# Switching_and_Pico.net
KiCad netlist of a schematic drawn in EAGLE
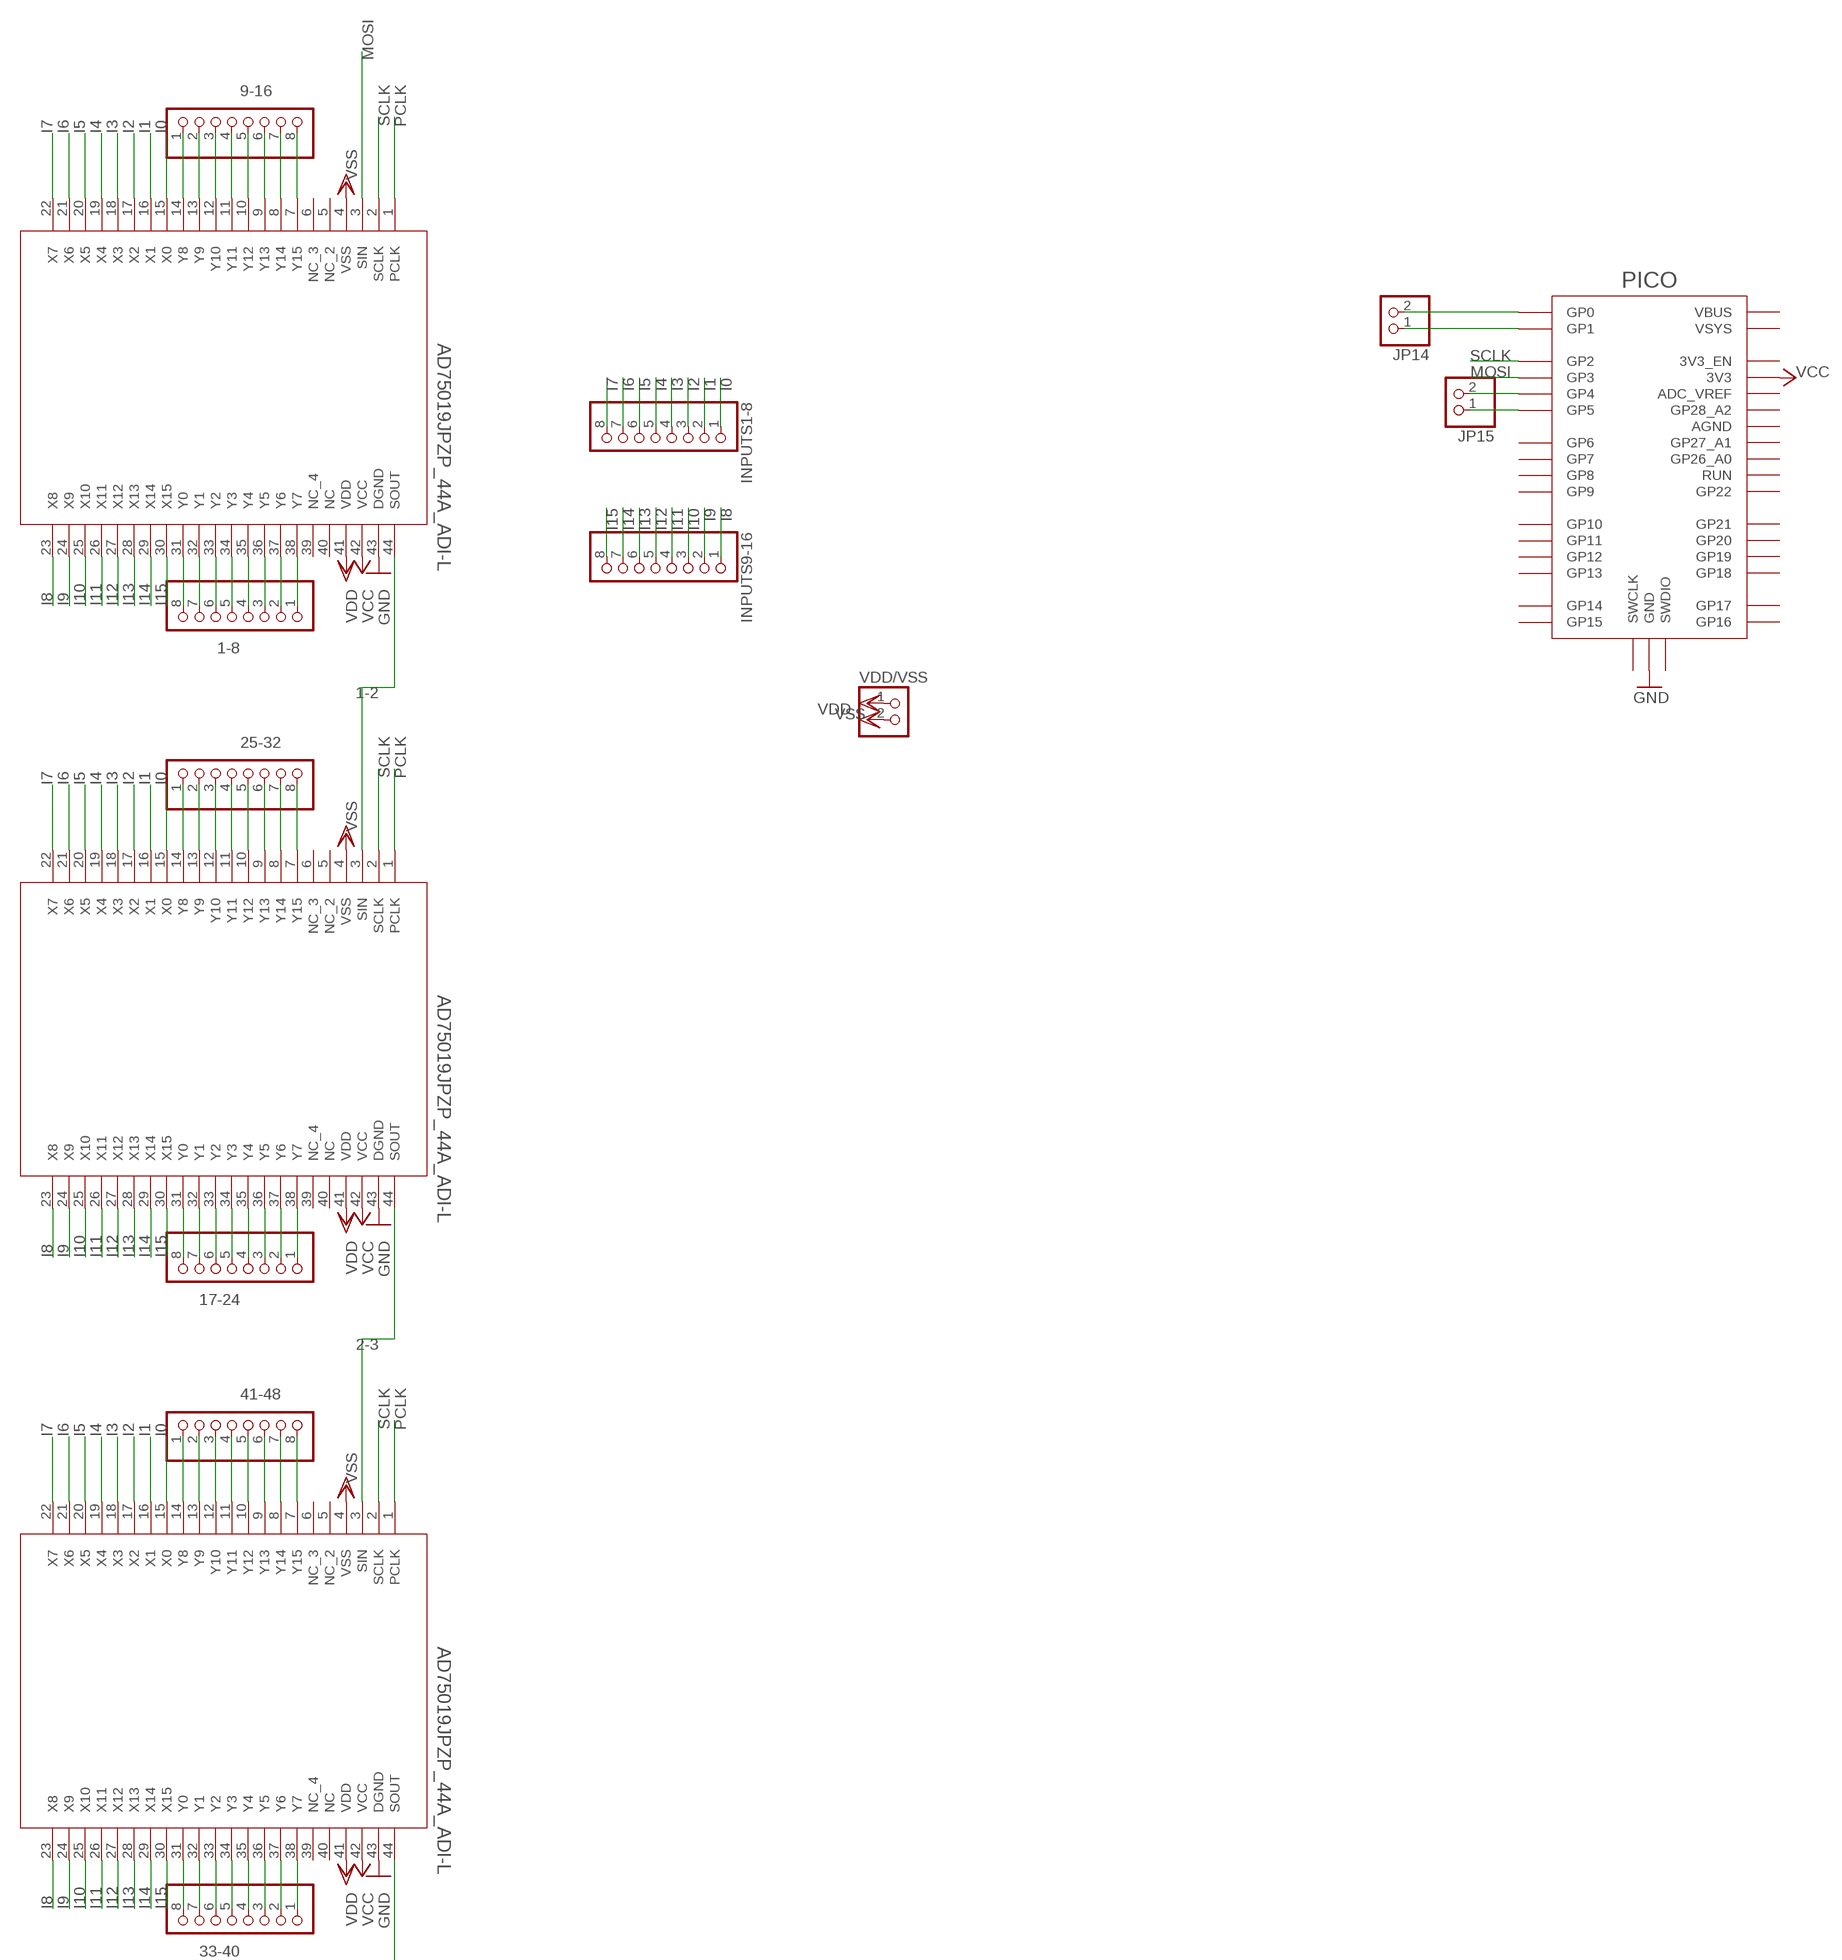
[diagram p0: schematic, sheet 1, part 1 of 2]
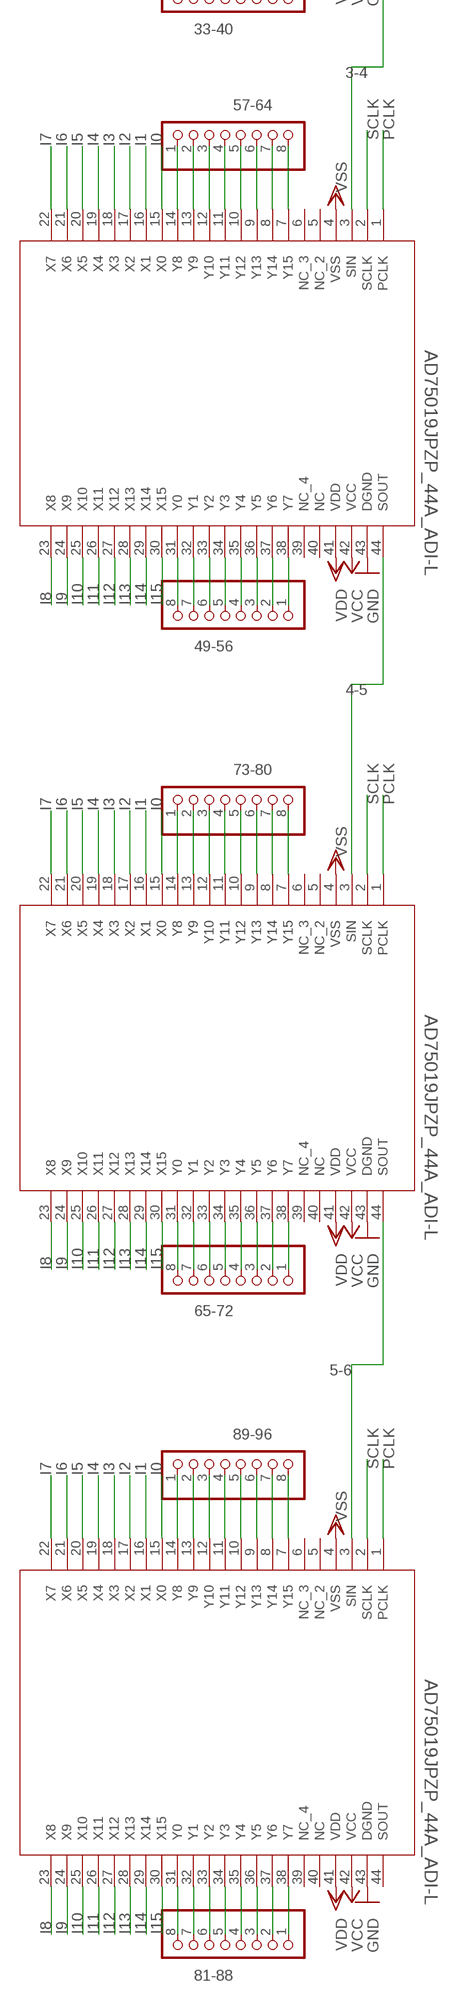
[diagram p1: schematic, sheet 1, part 2 of 2]

(export (version "E")
  (design (tool "Eeschema 10.0.6"))
  (components
    (comp (ref "1-8")
      (value "PINHD-1X8")
      (footprint "eagle-import:1X08")
      (libsource (lib "eagle-import") (part "PINHD-1X8"))
    )
    (comp (ref "9-16")
      (value "PINHD-1X8")
      (footprint "eagle-import:1X08")
      (libsource (lib "eagle-import") (part "PINHD-1X8"))
    )
    (comp (ref "17-24")
      (value "PINHD-1X8")
      (footprint "eagle-import:1X08")
      (libsource (lib "eagle-import") (part "PINHD-1X8"))
    )
    (comp (ref "25-32")
      (value "PINHD-1X8")
      (footprint "eagle-import:1X08")
      (libsource (lib "eagle-import") (part "PINHD-1X8"))
    )
    (comp (ref "33-40")
      (value "PINHD-1X8")
      (footprint "eagle-import:1X08")
      (libsource (lib "eagle-import") (part "PINHD-1X8"))
    )
    (comp (ref "41-48")
      (value "PINHD-1X8")
      (footprint "eagle-import:1X08")
      (libsource (lib "eagle-import") (part "PINHD-1X8"))
    )
    (comp (ref "49-56")
      (value "PINHD-1X8")
      (footprint "eagle-import:1X08")
      (libsource (lib "eagle-import") (part "PINHD-1X8"))
    )
    (comp (ref "57-64")
      (value "PINHD-1X8")
      (footprint "eagle-import:1X08")
      (libsource (lib "eagle-import") (part "PINHD-1X8"))
    )
    (comp (ref "65-72")
      (value "PINHD-1X8")
      (footprint "eagle-import:1X08")
      (libsource (lib "eagle-import") (part "PINHD-1X8"))
    )
    (comp (ref "73-80")
      (value "PINHD-1X8")
      (footprint "eagle-import:1X08")
      (libsource (lib "eagle-import") (part "PINHD-1X8"))
    )
    (comp (ref "81-88")
      (value "PINHD-1X8")
      (footprint "eagle-import:1X08")
      (libsource (lib "eagle-import") (part "PINHD-1X8"))
    )
    (comp (ref "89-96")
      (value "PINHD-1X8")
      (footprint "eagle-import:1X08")
      (libsource (lib "eagle-import") (part "PINHD-1X8"))
    )
    (comp (ref "INPUTS1-8")
      (value "PINHD-1X8")
      (footprint "eagle-import:1X08")
      (libsource (lib "eagle-import") (part "PINHD-1X8"))
    )
    (comp (ref "INPUTS9-16")
      (value "PINHD-1X8")
      (footprint "eagle-import:1X08")
      (libsource (lib "eagle-import") (part "PINHD-1X8"))
    )
    (comp (ref "JP14")
      (value "PINHD-1X2")
      (footprint "eagle-import:1X02")
      (libsource (lib "eagle-import") (part "PINHD-1X2"))
    )
    (comp (ref "JP15")
      (value "PINHD-1X2")
      (footprint "eagle-import:1X02")
      (libsource (lib "eagle-import") (part "PINHD-1X2"))
    )
    (comp (ref "PICO")
      (value "RPI_PICO-TH")
      (footprint "eagle-import:RPI_PICO_TH")
      (libsource (lib "eagle-import") (part "RPI_PICO-TH"))
    )
    (comp (ref "SWITCH1")
      (value "AD75019JPZP_44A_ADI-L")
      (footprint "eagle-import:P_44A_ADI-L")
      (fields
        (field (name "MANUFACTURER_PART_NUMBER") "AD75019JPZ")
        (field (name "COPYRIGHT") "Copyright (C) 2024 Ultra Librarian. All rights reserved.")
      )
      (libsource (lib "eagle-import") (part "AD75019JPZP_44A_ADI-L"))
    )
    (comp (ref "SWITCH2")
      (value "AD75019JPZP_44A_ADI-L")
      (footprint "eagle-import:P_44A_ADI-L")
      (fields
        (field (name "MANUFACTURER_PART_NUMBER") "AD75019JPZ")
        (field (name "COPYRIGHT") "Copyright (C) 2024 Ultra Librarian. All rights reserved.")
      )
      (libsource (lib "eagle-import") (part "AD75019JPZP_44A_ADI-L"))
    )
    (comp (ref "SWITCH3")
      (value "AD75019JPZP_44A_ADI-L")
      (footprint "eagle-import:P_44A_ADI-L")
      (fields
        (field (name "MANUFACTURER_PART_NUMBER") "AD75019JPZ")
        (field (name "COPYRIGHT") "Copyright (C) 2024 Ultra Librarian. All rights reserved.")
      )
      (libsource (lib "eagle-import") (part "AD75019JPZP_44A_ADI-L"))
    )
    (comp (ref "SWITCH4")
      (value "AD75019JPZP_44A_ADI-L")
      (footprint "eagle-import:P_44A_ADI-L")
      (fields
        (field (name "MANUFACTURER_PART_NUMBER") "AD75019JPZ")
        (field (name "COPYRIGHT") "Copyright (C) 2024 Ultra Librarian. All rights reserved.")
      )
      (libsource (lib "eagle-import") (part "AD75019JPZP_44A_ADI-L"))
    )
    (comp (ref "SWITCH5")
      (value "AD75019JPZP_44A_ADI-L")
      (footprint "eagle-import:P_44A_ADI-L")
      (fields
        (field (name "MANUFACTURER_PART_NUMBER") "AD75019JPZ")
        (field (name "COPYRIGHT") "Copyright (C) 2024 Ultra Librarian. All rights reserved.")
      )
      (libsource (lib "eagle-import") (part "AD75019JPZP_44A_ADI-L"))
    )
    (comp (ref "SWITCH6")
      (value "AD75019JPZP_44A_ADI-L")
      (footprint "eagle-import:P_44A_ADI-L")
      (fields
        (field (name "MANUFACTURER_PART_NUMBER") "AD75019JPZ")
        (field (name "COPYRIGHT") "Copyright (C) 2024 Ultra Librarian. All rights reserved.")
      )
      (libsource (lib "eagle-import") (part "AD75019JPZP_44A_ADI-L"))
    )
    (comp (ref "VDD/VSS")
      (value "PINHD-1X2")
      (footprint "eagle-import:1X02")
      (libsource (lib "eagle-import") (part "PINHD-1X2"))
    )
  )
  (nets
    (net (code "1") (name "/1-2") (class "Default")
      (node (ref "SWITCH1") (pin "44") (pinfunction "SOUT_44") (pintype "passive"))
      (node (ref "SWITCH2") (pin "3") (pinfunction "SIN_3") (pintype "passive"))
    )
    (net (code "2") (name "/2-3") (class "Default")
      (node (ref "SWITCH2") (pin "44") (pinfunction "SOUT_44") (pintype "passive"))
      (node (ref "SWITCH3") (pin "3") (pinfunction "SIN_3") (pintype "passive"))
    )
    (net (code "3") (name "/3-4") (class "Default")
      (node (ref "SWITCH3") (pin "44") (pinfunction "SOUT_44") (pintype "passive"))
      (node (ref "SWITCH4") (pin "3") (pinfunction "SIN_3") (pintype "passive"))
    )
    (net (code "4") (name "/4-5") (class "Default")
      (node (ref "SWITCH4") (pin "44") (pinfunction "SOUT_44") (pintype "passive"))
      (node (ref "SWITCH5") (pin "3") (pinfunction "SIN_3") (pintype "passive"))
    )
    (net (code "5") (name "/5-6") (class "Default")
      (node (ref "SWITCH5") (pin "44") (pinfunction "SOUT_44") (pintype "passive"))
      (node (ref "SWITCH6") (pin "3") (pinfunction "SIN_3") (pintype "passive"))
    )
    (net (code "6") (name "/I0") (class "Default")
      (node (ref "INPUTS1-8") (pin "1") (pinfunction "1_1") (pintype "passive"))
      (node (ref "SWITCH1") (pin "15") (pinfunction "X0_15") (pintype "passive"))
      (node (ref "SWITCH2") (pin "15") (pinfunction "X0_15") (pintype "passive"))
      (node (ref "SWITCH3") (pin "15") (pinfunction "X0_15") (pintype "passive"))
      (node (ref "SWITCH4") (pin "15") (pinfunction "X0_15") (pintype "passive"))
      (node (ref "SWITCH5") (pin "15") (pinfunction "X0_15") (pintype "passive"))
      (node (ref "SWITCH6") (pin "15") (pinfunction "X0_15") (pintype "passive"))
    )
    (net (code "7") (name "/I1") (class "Default")
      (node (ref "INPUTS1-8") (pin "2") (pinfunction "2_2") (pintype "passive"))
      (node (ref "SWITCH1") (pin "16") (pinfunction "X1_16") (pintype "passive"))
      (node (ref "SWITCH2") (pin "16") (pinfunction "X1_16") (pintype "passive"))
      (node (ref "SWITCH3") (pin "16") (pinfunction "X1_16") (pintype "passive"))
      (node (ref "SWITCH4") (pin "16") (pinfunction "X1_16") (pintype "passive"))
      (node (ref "SWITCH5") (pin "16") (pinfunction "X1_16") (pintype "passive"))
      (node (ref "SWITCH6") (pin "16") (pinfunction "X1_16") (pintype "passive"))
    )
    (net (code "8") (name "/I2") (class "Default")
      (node (ref "INPUTS1-8") (pin "3") (pinfunction "3_3") (pintype "passive"))
      (node (ref "SWITCH1") (pin "17") (pinfunction "X2_17") (pintype "passive"))
      (node (ref "SWITCH2") (pin "17") (pinfunction "X2_17") (pintype "passive"))
      (node (ref "SWITCH3") (pin "17") (pinfunction "X2_17") (pintype "passive"))
      (node (ref "SWITCH4") (pin "17") (pinfunction "X2_17") (pintype "passive"))
      (node (ref "SWITCH5") (pin "17") (pinfunction "X2_17") (pintype "passive"))
      (node (ref "SWITCH6") (pin "17") (pinfunction "X2_17") (pintype "passive"))
    )
    (net (code "9") (name "/I3") (class "Default")
      (node (ref "INPUTS1-8") (pin "4") (pinfunction "4_4") (pintype "passive"))
      (node (ref "SWITCH1") (pin "18") (pinfunction "X3_18") (pintype "passive"))
      (node (ref "SWITCH2") (pin "18") (pinfunction "X3_18") (pintype "passive"))
      (node (ref "SWITCH3") (pin "18") (pinfunction "X3_18") (pintype "passive"))
      (node (ref "SWITCH4") (pin "18") (pinfunction "X3_18") (pintype "passive"))
      (node (ref "SWITCH5") (pin "18") (pinfunction "X3_18") (pintype "passive"))
      (node (ref "SWITCH6") (pin "18") (pinfunction "X3_18") (pintype "passive"))
    )
    (net (code "10") (name "/I4") (class "Default")
      (node (ref "INPUTS1-8") (pin "5") (pinfunction "5_5") (pintype "passive"))
      (node (ref "SWITCH1") (pin "19") (pinfunction "X4_19") (pintype "passive"))
      (node (ref "SWITCH2") (pin "19") (pinfunction "X4_19") (pintype "passive"))
      (node (ref "SWITCH3") (pin "19") (pinfunction "X4_19") (pintype "passive"))
      (node (ref "SWITCH4") (pin "19") (pinfunction "X4_19") (pintype "passive"))
      (node (ref "SWITCH5") (pin "19") (pinfunction "X4_19") (pintype "passive"))
      (node (ref "SWITCH6") (pin "19") (pinfunction "X4_19") (pintype "passive"))
    )
    (net (code "11") (name "/I5") (class "Default")
      (node (ref "INPUTS1-8") (pin "6") (pinfunction "6_6") (pintype "passive"))
      (node (ref "SWITCH1") (pin "20") (pinfunction "X5_20") (pintype "passive"))
      (node (ref "SWITCH2") (pin "20") (pinfunction "X5_20") (pintype "passive"))
      (node (ref "SWITCH3") (pin "20") (pinfunction "X5_20") (pintype "passive"))
      (node (ref "SWITCH4") (pin "20") (pinfunction "X5_20") (pintype "passive"))
      (node (ref "SWITCH5") (pin "20") (pinfunction "X5_20") (pintype "passive"))
      (node (ref "SWITCH6") (pin "20") (pinfunction "X5_20") (pintype "passive"))
    )
    (net (code "12") (name "/I6") (class "Default")
      (node (ref "INPUTS1-8") (pin "7") (pinfunction "7_7") (pintype "passive"))
      (node (ref "SWITCH1") (pin "21") (pinfunction "X6_21") (pintype "passive"))
      (node (ref "SWITCH2") (pin "21") (pinfunction "X6_21") (pintype "passive"))
      (node (ref "SWITCH3") (pin "21") (pinfunction "X6_21") (pintype "passive"))
      (node (ref "SWITCH4") (pin "21") (pinfunction "X6_21") (pintype "passive"))
      (node (ref "SWITCH5") (pin "21") (pinfunction "X6_21") (pintype "passive"))
      (node (ref "SWITCH6") (pin "21") (pinfunction "X6_21") (pintype "passive"))
    )
    (net (code "13") (name "/I7") (class "Default")
      (node (ref "INPUTS1-8") (pin "8") (pinfunction "8_8") (pintype "passive"))
      (node (ref "SWITCH1") (pin "22") (pinfunction "X7_22") (pintype "passive"))
      (node (ref "SWITCH2") (pin "22") (pinfunction "X7_22") (pintype "passive"))
      (node (ref "SWITCH3") (pin "22") (pinfunction "X7_22") (pintype "passive"))
      (node (ref "SWITCH4") (pin "22") (pinfunction "X7_22") (pintype "passive"))
      (node (ref "SWITCH5") (pin "22") (pinfunction "X7_22") (pintype "passive"))
      (node (ref "SWITCH6") (pin "22") (pinfunction "X7_22") (pintype "passive"))
    )
    (net (code "14") (name "/I8") (class "Default")
      (node (ref "INPUTS9-16") (pin "1") (pinfunction "1_1") (pintype "passive"))
      (node (ref "SWITCH1") (pin "23") (pinfunction "X8_23") (pintype "passive"))
      (node (ref "SWITCH2") (pin "23") (pinfunction "X8_23") (pintype "passive"))
      (node (ref "SWITCH3") (pin "23") (pinfunction "X8_23") (pintype "passive"))
      (node (ref "SWITCH4") (pin "23") (pinfunction "X8_23") (pintype "passive"))
      (node (ref "SWITCH5") (pin "23") (pinfunction "X8_23") (pintype "passive"))
      (node (ref "SWITCH6") (pin "23") (pinfunction "X8_23") (pintype "passive"))
    )
    (net (code "15") (name "/I9") (class "Default")
      (node (ref "INPUTS9-16") (pin "2") (pinfunction "2_2") (pintype "passive"))
      (node (ref "SWITCH1") (pin "24") (pinfunction "X9_24") (pintype "passive"))
      (node (ref "SWITCH2") (pin "24") (pinfunction "X9_24") (pintype "passive"))
      (node (ref "SWITCH3") (pin "24") (pinfunction "X9_24") (pintype "passive"))
      (node (ref "SWITCH4") (pin "24") (pinfunction "X9_24") (pintype "passive"))
      (node (ref "SWITCH5") (pin "24") (pinfunction "X9_24") (pintype "passive"))
      (node (ref "SWITCH6") (pin "24") (pinfunction "X9_24") (pintype "passive"))
    )
    (net (code "16") (name "/I10") (class "Default")
      (node (ref "INPUTS9-16") (pin "3") (pinfunction "3_3") (pintype "passive"))
      (node (ref "SWITCH1") (pin "25") (pinfunction "X10_25") (pintype "passive"))
      (node (ref "SWITCH2") (pin "25") (pinfunction "X10_25") (pintype "passive"))
      (node (ref "SWITCH3") (pin "25") (pinfunction "X10_25") (pintype "passive"))
      (node (ref "SWITCH4") (pin "25") (pinfunction "X10_25") (pintype "passive"))
      (node (ref "SWITCH5") (pin "25") (pinfunction "X10_25") (pintype "passive"))
      (node (ref "SWITCH6") (pin "25") (pinfunction "X10_25") (pintype "passive"))
    )
    (net (code "17") (name "/I11") (class "Default")
      (node (ref "INPUTS9-16") (pin "4") (pinfunction "4_4") (pintype "passive"))
      (node (ref "SWITCH1") (pin "26") (pinfunction "X11_26") (pintype "passive"))
      (node (ref "SWITCH2") (pin "26") (pinfunction "X11_26") (pintype "passive"))
      (node (ref "SWITCH3") (pin "26") (pinfunction "X11_26") (pintype "passive"))
      (node (ref "SWITCH4") (pin "26") (pinfunction "X11_26") (pintype "passive"))
      (node (ref "SWITCH5") (pin "26") (pinfunction "X11_26") (pintype "passive"))
      (node (ref "SWITCH6") (pin "26") (pinfunction "X11_26") (pintype "passive"))
    )
    (net (code "18") (name "/I12") (class "Default")
      (node (ref "INPUTS9-16") (pin "5") (pinfunction "5_5") (pintype "passive"))
      (node (ref "SWITCH1") (pin "27") (pinfunction "X12_27") (pintype "passive"))
      (node (ref "SWITCH2") (pin "27") (pinfunction "X12_27") (pintype "passive"))
      (node (ref "SWITCH3") (pin "27") (pinfunction "X12_27") (pintype "passive"))
      (node (ref "SWITCH4") (pin "27") (pinfunction "X12_27") (pintype "passive"))
      (node (ref "SWITCH5") (pin "27") (pinfunction "X12_27") (pintype "passive"))
      (node (ref "SWITCH6") (pin "27") (pinfunction "X12_27") (pintype "passive"))
    )
    (net (code "19") (name "/I13") (class "Default")
      (node (ref "INPUTS9-16") (pin "6") (pinfunction "6_6") (pintype "passive"))
      (node (ref "SWITCH1") (pin "28") (pinfunction "X13_28") (pintype "passive"))
      (node (ref "SWITCH2") (pin "28") (pinfunction "X13_28") (pintype "passive"))
      (node (ref "SWITCH3") (pin "28") (pinfunction "X13_28") (pintype "passive"))
      (node (ref "SWITCH4") (pin "28") (pinfunction "X13_28") (pintype "passive"))
      (node (ref "SWITCH5") (pin "28") (pinfunction "X13_28") (pintype "passive"))
      (node (ref "SWITCH6") (pin "28") (pinfunction "X13_28") (pintype "passive"))
    )
    (net (code "20") (name "/I14") (class "Default")
      (node (ref "INPUTS9-16") (pin "7") (pinfunction "7_7") (pintype "passive"))
      (node (ref "SWITCH1") (pin "29") (pinfunction "X14_29") (pintype "passive"))
      (node (ref "SWITCH2") (pin "29") (pinfunction "X14_29") (pintype "passive"))
      (node (ref "SWITCH3") (pin "29") (pinfunction "X14_29") (pintype "passive"))
      (node (ref "SWITCH4") (pin "29") (pinfunction "X14_29") (pintype "passive"))
      (node (ref "SWITCH5") (pin "29") (pinfunction "X14_29") (pintype "passive"))
      (node (ref "SWITCH6") (pin "29") (pinfunction "X14_29") (pintype "passive"))
    )
    (net (code "21") (name "/I15") (class "Default")
      (node (ref "INPUTS9-16") (pin "8") (pinfunction "8_8") (pintype "passive"))
      (node (ref "SWITCH1") (pin "30") (pinfunction "X15_30") (pintype "passive"))
      (node (ref "SWITCH2") (pin "30") (pinfunction "X15_30") (pintype "passive"))
      (node (ref "SWITCH3") (pin "30") (pinfunction "X15_30") (pintype "passive"))
      (node (ref "SWITCH4") (pin "30") (pinfunction "X15_30") (pintype "passive"))
      (node (ref "SWITCH5") (pin "30") (pinfunction "X15_30") (pintype "passive"))
      (node (ref "SWITCH6") (pin "30") (pinfunction "X15_30") (pintype "passive"))
    )
    (net (code "22") (name "/MOSI") (class "Default")
      (node (ref "PICO") (pin "GP3") (pinfunction "GP3_GP3") (pintype "bidirectional"))
      (node (ref "SWITCH1") (pin "3") (pinfunction "SIN_3") (pintype "passive"))
    )
    (net (code "23") (name "/PCLK") (class "Default")
      (node (ref "SWITCH1") (pin "1") (pinfunction "PCLK_1") (pintype "passive"))
      (node (ref "SWITCH2") (pin "1") (pinfunction "PCLK_1") (pintype "passive"))
      (node (ref "SWITCH3") (pin "1") (pinfunction "PCLK_1") (pintype "passive"))
      (node (ref "SWITCH4") (pin "1") (pinfunction "PCLK_1") (pintype "passive"))
      (node (ref "SWITCH5") (pin "1") (pinfunction "PCLK_1") (pintype "passive"))
      (node (ref "SWITCH6") (pin "1") (pinfunction "PCLK_1") (pintype "passive"))
    )
    (net (code "24") (name "/SCLK") (class "Default")
      (node (ref "PICO") (pin "GP2") (pinfunction "GP2_GP2") (pintype "bidirectional"))
      (node (ref "SWITCH1") (pin "2") (pinfunction "SCLK_2") (pintype "passive"))
      (node (ref "SWITCH2") (pin "2") (pinfunction "SCLK_2") (pintype "passive"))
      (node (ref "SWITCH3") (pin "2") (pinfunction "SCLK_2") (pintype "passive"))
      (node (ref "SWITCH4") (pin "2") (pinfunction "SCLK_2") (pintype "passive"))
      (node (ref "SWITCH5") (pin "2") (pinfunction "SCLK_2") (pintype "passive"))
      (node (ref "SWITCH6") (pin "2") (pinfunction "SCLK_2") (pintype "passive"))
    )
    (net (code "25") (name "GND") (class "Default")
      (node (ref "PICO") (pin "GND@1") (pinfunction "GND_GND@1") (pintype "bidirectional"))
      (node (ref "PICO") (pin "GND@2") (pinfunction "GND_GND@2") (pintype "bidirectional"))
      (node (ref "PICO") (pin "GND@3") (pinfunction "GND_GND@3") (pintype "bidirectional"))
      (node (ref "PICO") (pin "GND@4") (pinfunction "GND_GND@4") (pintype "bidirectional"))
      (node (ref "PICO") (pin "GND@5") (pinfunction "GND_GND@5") (pintype "bidirectional"))
      (node (ref "PICO") (pin "GND@6") (pinfunction "GND_GND@6") (pintype "bidirectional"))
      (node (ref "PICO") (pin "GND@7") (pinfunction "GND_GND@7") (pintype "bidirectional"))
      (node (ref "PICO") (pin "GND@8") (pinfunction "GND_GND@8") (pintype "bidirectional"))
      (node (ref "SWITCH1") (pin "43") (pinfunction "DGND_43") (pintype "passive"))
      (node (ref "SWITCH2") (pin "43") (pinfunction "DGND_43") (pintype "passive"))
      (node (ref "SWITCH3") (pin "43") (pinfunction "DGND_43") (pintype "passive"))
      (node (ref "SWITCH4") (pin "43") (pinfunction "DGND_43") (pintype "passive"))
      (node (ref "SWITCH5") (pin "43") (pinfunction "DGND_43") (pintype "passive"))
      (node (ref "SWITCH6") (pin "43") (pinfunction "DGND_43") (pintype "passive"))
    )
    (net (code "26") (name "Net-(JP14-Pad1)") (class "Default")
      (node (ref "JP14") (pin "1") (pinfunction "1_1") (pintype "passive"))
      (node (ref "PICO") (pin "GP1") (pinfunction "GP1_GP1") (pintype "bidirectional"))
    )
    (net (code "27") (name "Net-(JP14-Pad2)") (class "Default")
      (node (ref "JP14") (pin "2") (pinfunction "2_2") (pintype "passive"))
      (node (ref "PICO") (pin "GP0") (pinfunction "GP0_GP0") (pintype "bidirectional"))
    )
    (net (code "28") (name "Net-(JP15-Pad1)") (class "Default")
      (node (ref "JP15") (pin "1") (pinfunction "1_1") (pintype "passive"))
      (node (ref "PICO") (pin "GP5") (pinfunction "GP5_GP5") (pintype "bidirectional"))
    )
    (net (code "29") (name "Net-(JP15-Pad2)") (class "Default")
      (node (ref "JP15") (pin "2") (pinfunction "2_2") (pintype "passive"))
      (node (ref "PICO") (pin "GP4") (pinfunction "GP4_GP4") (pintype "bidirectional"))
    )
    (net (code "30") (name "Net-(SWITCH1-Y0)") (class "Default")
      (node (ref "1-8") (pin "8") (pinfunction "8_8") (pintype "passive"))
      (node (ref "SWITCH1") (pin "31") (pinfunction "Y0_31") (pintype "passive"))
    )
    (net (code "31") (name "Net-(SWITCH1-Y1)") (class "Default")
      (node (ref "1-8") (pin "7") (pinfunction "7_7") (pintype "passive"))
      (node (ref "SWITCH1") (pin "32") (pinfunction "Y1_32") (pintype "passive"))
    )
    (net (code "32") (name "Net-(SWITCH1-Y2)") (class "Default")
      (node (ref "1-8") (pin "6") (pinfunction "6_6") (pintype "passive"))
      (node (ref "SWITCH1") (pin "33") (pinfunction "Y2_33") (pintype "passive"))
    )
    (net (code "33") (name "Net-(SWITCH1-Y3)") (class "Default")
      (node (ref "1-8") (pin "5") (pinfunction "5_5") (pintype "passive"))
      (node (ref "SWITCH1") (pin "34") (pinfunction "Y3_34") (pintype "passive"))
    )
    (net (code "34") (name "Net-(SWITCH1-Y4)") (class "Default")
      (node (ref "1-8") (pin "4") (pinfunction "4_4") (pintype "passive"))
      (node (ref "SWITCH1") (pin "35") (pinfunction "Y4_35") (pintype "passive"))
    )
    (net (code "35") (name "Net-(SWITCH1-Y5)") (class "Default")
      (node (ref "1-8") (pin "3") (pinfunction "3_3") (pintype "passive"))
      (node (ref "SWITCH1") (pin "36") (pinfunction "Y5_36") (pintype "passive"))
    )
    (net (code "36") (name "Net-(SWITCH1-Y6)") (class "Default")
      (node (ref "1-8") (pin "2") (pinfunction "2_2") (pintype "passive"))
      (node (ref "SWITCH1") (pin "37") (pinfunction "Y6_37") (pintype "passive"))
    )
    (net (code "37") (name "Net-(SWITCH1-Y7)") (class "Default")
      (node (ref "1-8") (pin "1") (pinfunction "1_1") (pintype "passive"))
      (node (ref "SWITCH1") (pin "38") (pinfunction "Y7_38") (pintype "passive"))
    )
    (net (code "38") (name "Net-(SWITCH1-Y8)") (class "Default")
      (node (ref "9-16") (pin "1") (pinfunction "1_1") (pintype "passive"))
      (node (ref "SWITCH1") (pin "14") (pinfunction "Y8_14") (pintype "passive"))
    )
    (net (code "39") (name "Net-(SWITCH1-Y9)") (class "Default")
      (node (ref "9-16") (pin "2") (pinfunction "2_2") (pintype "passive"))
      (node (ref "SWITCH1") (pin "13") (pinfunction "Y9_13") (pintype "passive"))
    )
    (net (code "40") (name "Net-(SWITCH1-Y10)") (class "Default")
      (node (ref "9-16") (pin "3") (pinfunction "3_3") (pintype "passive"))
      (node (ref "SWITCH1") (pin "12") (pinfunction "Y10_12") (pintype "passive"))
    )
    (net (code "41") (name "Net-(SWITCH1-Y11)") (class "Default")
      (node (ref "9-16") (pin "4") (pinfunction "4_4") (pintype "passive"))
      (node (ref "SWITCH1") (pin "11") (pinfunction "Y11_11") (pintype "passive"))
    )
    (net (code "42") (name "Net-(SWITCH1-Y12)") (class "Default")
      (node (ref "9-16") (pin "5") (pinfunction "5_5") (pintype "passive"))
      (node (ref "SWITCH1") (pin "10") (pinfunction "Y12_10") (pintype "passive"))
    )
    (net (code "43") (name "Net-(SWITCH1-Y13)") (class "Default")
      (node (ref "9-16") (pin "6") (pinfunction "6_6") (pintype "passive"))
      (node (ref "SWITCH1") (pin "9") (pinfunction "Y13_9") (pintype "passive"))
    )
    (net (code "44") (name "Net-(SWITCH1-Y14)") (class "Default")
      (node (ref "9-16") (pin "7") (pinfunction "7_7") (pintype "passive"))
      (node (ref "SWITCH1") (pin "8") (pinfunction "Y14_8") (pintype "passive"))
    )
    (net (code "45") (name "Net-(SWITCH1-Y15)") (class "Default")
      (node (ref "9-16") (pin "8") (pinfunction "8_8") (pintype "passive"))
      (node (ref "SWITCH1") (pin "7") (pinfunction "Y15_7") (pintype "passive"))
    )
    (net (code "46") (name "Net-(SWITCH2-Y0)") (class "Default")
      (node (ref "17-24") (pin "8") (pinfunction "8_8") (pintype "passive"))
      (node (ref "SWITCH2") (pin "31") (pinfunction "Y0_31") (pintype "passive"))
    )
    (net (code "47") (name "Net-(SWITCH2-Y1)") (class "Default")
      (node (ref "17-24") (pin "7") (pinfunction "7_7") (pintype "passive"))
      (node (ref "SWITCH2") (pin "32") (pinfunction "Y1_32") (pintype "passive"))
    )
    (net (code "48") (name "Net-(SWITCH2-Y2)") (class "Default")
      (node (ref "17-24") (pin "6") (pinfunction "6_6") (pintype "passive"))
      (node (ref "SWITCH2") (pin "33") (pinfunction "Y2_33") (pintype "passive"))
    )
    (net (code "49") (name "Net-(SWITCH2-Y3)") (class "Default")
      (node (ref "17-24") (pin "5") (pinfunction "5_5") (pintype "passive"))
      (node (ref "SWITCH2") (pin "34") (pinfunction "Y3_34") (pintype "passive"))
    )
    (net (code "50") (name "Net-(SWITCH2-Y4)") (class "Default")
      (node (ref "17-24") (pin "4") (pinfunction "4_4") (pintype "passive"))
      (node (ref "SWITCH2") (pin "35") (pinfunction "Y4_35") (pintype "passive"))
    )
    (net (code "51") (name "Net-(SWITCH2-Y5)") (class "Default")
      (node (ref "17-24") (pin "3") (pinfunction "3_3") (pintype "passive"))
      (node (ref "SWITCH2") (pin "36") (pinfunction "Y5_36") (pintype "passive"))
    )
    (net (code "52") (name "Net-(SWITCH2-Y6)") (class "Default")
      (node (ref "17-24") (pin "2") (pinfunction "2_2") (pintype "passive"))
      (node (ref "SWITCH2") (pin "37") (pinfunction "Y6_37") (pintype "passive"))
    )
    (net (code "53") (name "Net-(SWITCH2-Y7)") (class "Default")
      (node (ref "17-24") (pin "1") (pinfunction "1_1") (pintype "passive"))
      (node (ref "SWITCH2") (pin "38") (pinfunction "Y7_38") (pintype "passive"))
    )
    (net (code "54") (name "Net-(SWITCH2-Y8)") (class "Default")
      (node (ref "25-32") (pin "1") (pinfunction "1_1") (pintype "passive"))
      (node (ref "SWITCH2") (pin "14") (pinfunction "Y8_14") (pintype "passive"))
    )
    (net (code "55") (name "Net-(SWITCH2-Y9)") (class "Default")
      (node (ref "25-32") (pin "2") (pinfunction "2_2") (pintype "passive"))
      (node (ref "SWITCH2") (pin "13") (pinfunction "Y9_13") (pintype "passive"))
    )
    (net (code "56") (name "Net-(SWITCH2-Y10)") (class "Default")
      (node (ref "25-32") (pin "3") (pinfunction "3_3") (pintype "passive"))
      (node (ref "SWITCH2") (pin "12") (pinfunction "Y10_12") (pintype "passive"))
    )
    (net (code "57") (name "Net-(SWITCH2-Y11)") (class "Default")
      (node (ref "25-32") (pin "4") (pinfunction "4_4") (pintype "passive"))
      (node (ref "SWITCH2") (pin "11") (pinfunction "Y11_11") (pintype "passive"))
    )
    (net (code "58") (name "Net-(SWITCH2-Y12)") (class "Default")
      (node (ref "25-32") (pin "5") (pinfunction "5_5") (pintype "passive"))
      (node (ref "SWITCH2") (pin "10") (pinfunction "Y12_10") (pintype "passive"))
    )
    (net (code "59") (name "Net-(SWITCH2-Y13)") (class "Default")
      (node (ref "25-32") (pin "6") (pinfunction "6_6") (pintype "passive"))
      (node (ref "SWITCH2") (pin "9") (pinfunction "Y13_9") (pintype "passive"))
    )
    (net (code "60") (name "Net-(SWITCH2-Y14)") (class "Default")
      (node (ref "25-32") (pin "7") (pinfunction "7_7") (pintype "passive"))
      (node (ref "SWITCH2") (pin "8") (pinfunction "Y14_8") (pintype "passive"))
    )
    (net (code "61") (name "Net-(SWITCH2-Y15)") (class "Default")
      (node (ref "25-32") (pin "8") (pinfunction "8_8") (pintype "passive"))
      (node (ref "SWITCH2") (pin "7") (pinfunction "Y15_7") (pintype "passive"))
    )
    (net (code "62") (name "Net-(SWITCH3-Y0)") (class "Default")
      (node (ref "33-40") (pin "8") (pinfunction "8_8") (pintype "passive"))
      (node (ref "SWITCH3") (pin "31") (pinfunction "Y0_31") (pintype "passive"))
    )
    (net (code "63") (name "Net-(SWITCH3-Y1)") (class "Default")
      (node (ref "33-40") (pin "7") (pinfunction "7_7") (pintype "passive"))
      (node (ref "SWITCH3") (pin "32") (pinfunction "Y1_32") (pintype "passive"))
    )
    (net (code "64") (name "Net-(SWITCH3-Y2)") (class "Default")
      (node (ref "33-40") (pin "6") (pinfunction "6_6") (pintype "passive"))
      (node (ref "SWITCH3") (pin "33") (pinfunction "Y2_33") (pintype "passive"))
    )
    (net (code "65") (name "Net-(SWITCH3-Y3)") (class "Default")
      (node (ref "33-40") (pin "5") (pinfunction "5_5") (pintype "passive"))
      (node (ref "SWITCH3") (pin "34") (pinfunction "Y3_34") (pintype "passive"))
    )
    (net (code "66") (name "Net-(SWITCH3-Y4)") (class "Default")
      (node (ref "33-40") (pin "4") (pinfunction "4_4") (pintype "passive"))
      (node (ref "SWITCH3") (pin "35") (pinfunction "Y4_35") (pintype "passive"))
    )
    (net (code "67") (name "Net-(SWITCH3-Y5)") (class "Default")
      (node (ref "33-40") (pin "3") (pinfunction "3_3") (pintype "passive"))
      (node (ref "SWITCH3") (pin "36") (pinfunction "Y5_36") (pintype "passive"))
    )
    (net (code "68") (name "Net-(SWITCH3-Y6)") (class "Default")
      (node (ref "33-40") (pin "2") (pinfunction "2_2") (pintype "passive"))
      (node (ref "SWITCH3") (pin "37") (pinfunction "Y6_37") (pintype "passive"))
    )
    (net (code "69") (name "Net-(SWITCH3-Y7)") (class "Default")
      (node (ref "33-40") (pin "1") (pinfunction "1_1") (pintype "passive"))
      (node (ref "SWITCH3") (pin "38") (pinfunction "Y7_38") (pintype "passive"))
    )
    (net (code "70") (name "Net-(SWITCH3-Y8)") (class "Default")
      (node (ref "41-48") (pin "1") (pinfunction "1_1") (pintype "passive"))
      (node (ref "SWITCH3") (pin "14") (pinfunction "Y8_14") (pintype "passive"))
    )
    (net (code "71") (name "Net-(SWITCH3-Y9)") (class "Default")
      (node (ref "41-48") (pin "2") (pinfunction "2_2") (pintype "passive"))
      (node (ref "SWITCH3") (pin "13") (pinfunction "Y9_13") (pintype "passive"))
    )
    (net (code "72") (name "Net-(SWITCH3-Y10)") (class "Default")
      (node (ref "41-48") (pin "3") (pinfunction "3_3") (pintype "passive"))
      (node (ref "SWITCH3") (pin "12") (pinfunction "Y10_12") (pintype "passive"))
    )
    (net (code "73") (name "Net-(SWITCH3-Y11)") (class "Default")
      (node (ref "41-48") (pin "4") (pinfunction "4_4") (pintype "passive"))
      (node (ref "SWITCH3") (pin "11") (pinfunction "Y11_11") (pintype "passive"))
    )
    (net (code "74") (name "Net-(SWITCH3-Y12)") (class "Default")
      (node (ref "41-48") (pin "5") (pinfunction "5_5") (pintype "passive"))
      (node (ref "SWITCH3") (pin "10") (pinfunction "Y12_10") (pintype "passive"))
    )
    (net (code "75") (name "Net-(SWITCH3-Y13)") (class "Default")
      (node (ref "41-48") (pin "6") (pinfunction "6_6") (pintype "passive"))
      (node (ref "SWITCH3") (pin "9") (pinfunction "Y13_9") (pintype "passive"))
    )
    (net (code "76") (name "Net-(SWITCH3-Y14)") (class "Default")
      (node (ref "41-48") (pin "7") (pinfunction "7_7") (pintype "passive"))
      (node (ref "SWITCH3") (pin "8") (pinfunction "Y14_8") (pintype "passive"))
    )
    (net (code "77") (name "Net-(SWITCH3-Y15)") (class "Default")
      (node (ref "41-48") (pin "8") (pinfunction "8_8") (pintype "passive"))
      (node (ref "SWITCH3") (pin "7") (pinfunction "Y15_7") (pintype "passive"))
    )
    (net (code "78") (name "Net-(SWITCH4-Y0)") (class "Default")
      (node (ref "49-56") (pin "8") (pinfunction "8_8") (pintype "passive"))
      (node (ref "SWITCH4") (pin "31") (pinfunction "Y0_31") (pintype "passive"))
    )
    (net (code "79") (name "Net-(SWITCH4-Y1)") (class "Default")
      (node (ref "49-56") (pin "7") (pinfunction "7_7") (pintype "passive"))
      (node (ref "SWITCH4") (pin "32") (pinfunction "Y1_32") (pintype "passive"))
    )
    (net (code "80") (name "Net-(SWITCH4-Y2)") (class "Default")
      (node (ref "49-56") (pin "6") (pinfunction "6_6") (pintype "passive"))
      (node (ref "SWITCH4") (pin "33") (pinfunction "Y2_33") (pintype "passive"))
    )
    (net (code "81") (name "Net-(SWITCH4-Y3)") (class "Default")
      (node (ref "49-56") (pin "5") (pinfunction "5_5") (pintype "passive"))
      (node (ref "SWITCH4") (pin "34") (pinfunction "Y3_34") (pintype "passive"))
    )
    (net (code "82") (name "Net-(SWITCH4-Y4)") (class "Default")
      (node (ref "49-56") (pin "4") (pinfunction "4_4") (pintype "passive"))
      (node (ref "SWITCH4") (pin "35") (pinfunction "Y4_35") (pintype "passive"))
    )
    (net (code "83") (name "Net-(SWITCH4-Y5)") (class "Default")
      (node (ref "49-56") (pin "3") (pinfunction "3_3") (pintype "passive"))
      (node (ref "SWITCH4") (pin "36") (pinfunction "Y5_36") (pintype "passive"))
    )
    (net (code "84") (name "Net-(SWITCH4-Y6)") (class "Default")
      (node (ref "49-56") (pin "2") (pinfunction "2_2") (pintype "passive"))
      (node (ref "SWITCH4") (pin "37") (pinfunction "Y6_37") (pintype "passive"))
    )
    (net (code "85") (name "Net-(SWITCH4-Y7)") (class "Default")
      (node (ref "49-56") (pin "1") (pinfunction "1_1") (pintype "passive"))
      (node (ref "SWITCH4") (pin "38") (pinfunction "Y7_38") (pintype "passive"))
    )
    (net (code "86") (name "Net-(SWITCH4-Y8)") (class "Default")
      (node (ref "57-64") (pin "1") (pinfunction "1_1") (pintype "passive"))
      (node (ref "SWITCH4") (pin "14") (pinfunction "Y8_14") (pintype "passive"))
    )
    (net (code "87") (name "Net-(SWITCH4-Y9)") (class "Default")
      (node (ref "57-64") (pin "2") (pinfunction "2_2") (pintype "passive"))
      (node (ref "SWITCH4") (pin "13") (pinfunction "Y9_13") (pintype "passive"))
    )
    (net (code "88") (name "Net-(SWITCH4-Y10)") (class "Default")
      (node (ref "57-64") (pin "3") (pinfunction "3_3") (pintype "passive"))
      (node (ref "SWITCH4") (pin "12") (pinfunction "Y10_12") (pintype "passive"))
    )
    (net (code "89") (name "Net-(SWITCH4-Y11)") (class "Default")
      (node (ref "57-64") (pin "4") (pinfunction "4_4") (pintype "passive"))
      (node (ref "SWITCH4") (pin "11") (pinfunction "Y11_11") (pintype "passive"))
    )
    (net (code "90") (name "Net-(SWITCH4-Y12)") (class "Default")
      (node (ref "57-64") (pin "5") (pinfunction "5_5") (pintype "passive"))
      (node (ref "SWITCH4") (pin "10") (pinfunction "Y12_10") (pintype "passive"))
    )
    (net (code "91") (name "Net-(SWITCH4-Y13)") (class "Default")
      (node (ref "57-64") (pin "6") (pinfunction "6_6") (pintype "passive"))
      (node (ref "SWITCH4") (pin "9") (pinfunction "Y13_9") (pintype "passive"))
    )
    (net (code "92") (name "Net-(SWITCH4-Y14)") (class "Default")
      (node (ref "57-64") (pin "7") (pinfunction "7_7") (pintype "passive"))
      (node (ref "SWITCH4") (pin "8") (pinfunction "Y14_8") (pintype "passive"))
    )
    (net (code "93") (name "Net-(SWITCH4-Y15)") (class "Default")
      (node (ref "57-64") (pin "8") (pinfunction "8_8") (pintype "passive"))
      (node (ref "SWITCH4") (pin "7") (pinfunction "Y15_7") (pintype "passive"))
    )
    (net (code "94") (name "Net-(SWITCH5-Y0)") (class "Default")
      (node (ref "65-72") (pin "8") (pinfunction "8_8") (pintype "passive"))
      (node (ref "SWITCH5") (pin "31") (pinfunction "Y0_31") (pintype "passive"))
    )
    (net (code "95") (name "Net-(SWITCH5-Y1)") (class "Default")
      (node (ref "65-72") (pin "7") (pinfunction "7_7") (pintype "passive"))
      (node (ref "SWITCH5") (pin "32") (pinfunction "Y1_32") (pintype "passive"))
    )
    (net (code "96") (name "Net-(SWITCH5-Y2)") (class "Default")
      (node (ref "65-72") (pin "6") (pinfunction "6_6") (pintype "passive"))
      (node (ref "SWITCH5") (pin "33") (pinfunction "Y2_33") (pintype "passive"))
    )
    (net (code "97") (name "Net-(SWITCH5-Y3)") (class "Default")
      (node (ref "65-72") (pin "5") (pinfunction "5_5") (pintype "passive"))
      (node (ref "SWITCH5") (pin "34") (pinfunction "Y3_34") (pintype "passive"))
    )
    (net (code "98") (name "Net-(SWITCH5-Y4)") (class "Default")
      (node (ref "65-72") (pin "4") (pinfunction "4_4") (pintype "passive"))
      (node (ref "SWITCH5") (pin "35") (pinfunction "Y4_35") (pintype "passive"))
    )
    (net (code "99") (name "Net-(SWITCH5-Y5)") (class "Default")
      (node (ref "65-72") (pin "3") (pinfunction "3_3") (pintype "passive"))
      (node (ref "SWITCH5") (pin "36") (pinfunction "Y5_36") (pintype "passive"))
    )
    (net (code "100") (name "Net-(SWITCH5-Y6)") (class "Default")
      (node (ref "65-72") (pin "2") (pinfunction "2_2") (pintype "passive"))
      (node (ref "SWITCH5") (pin "37") (pinfunction "Y6_37") (pintype "passive"))
    )
    (net (code "101") (name "Net-(SWITCH5-Y7)") (class "Default")
      (node (ref "65-72") (pin "1") (pinfunction "1_1") (pintype "passive"))
      (node (ref "SWITCH5") (pin "38") (pinfunction "Y7_38") (pintype "passive"))
    )
    (net (code "102") (name "Net-(SWITCH5-Y8)") (class "Default")
      (node (ref "73-80") (pin "1") (pinfunction "1_1") (pintype "passive"))
      (node (ref "SWITCH5") (pin "14") (pinfunction "Y8_14") (pintype "passive"))
    )
    (net (code "103") (name "Net-(SWITCH5-Y9)") (class "Default")
      (node (ref "73-80") (pin "2") (pinfunction "2_2") (pintype "passive"))
      (node (ref "SWITCH5") (pin "13") (pinfunction "Y9_13") (pintype "passive"))
    )
    (net (code "104") (name "Net-(SWITCH5-Y10)") (class "Default")
      (node (ref "73-80") (pin "3") (pinfunction "3_3") (pintype "passive"))
      (node (ref "SWITCH5") (pin "12") (pinfunction "Y10_12") (pintype "passive"))
    )
    (net (code "105") (name "Net-(SWITCH5-Y11)") (class "Default")
      (node (ref "73-80") (pin "4") (pinfunction "4_4") (pintype "passive"))
      (node (ref "SWITCH5") (pin "11") (pinfunction "Y11_11") (pintype "passive"))
    )
    (net (code "106") (name "Net-(SWITCH5-Y12)") (class "Default")
      (node (ref "73-80") (pin "5") (pinfunction "5_5") (pintype "passive"))
      (node (ref "SWITCH5") (pin "10") (pinfunction "Y12_10") (pintype "passive"))
    )
    (net (code "107") (name "Net-(SWITCH5-Y13)") (class "Default")
      (node (ref "73-80") (pin "6") (pinfunction "6_6") (pintype "passive"))
      (node (ref "SWITCH5") (pin "9") (pinfunction "Y13_9") (pintype "passive"))
    )
    (net (code "108") (name "Net-(SWITCH5-Y14)") (class "Default")
      (node (ref "73-80") (pin "7") (pinfunction "7_7") (pintype "passive"))
      (node (ref "SWITCH5") (pin "8") (pinfunction "Y14_8") (pintype "passive"))
    )
    (net (code "109") (name "Net-(SWITCH5-Y15)") (class "Default")
      (node (ref "73-80") (pin "8") (pinfunction "8_8") (pintype "passive"))
      (node (ref "SWITCH5") (pin "7") (pinfunction "Y15_7") (pintype "passive"))
    )
    (net (code "110") (name "Net-(SWITCH6-Y0)") (class "Default")
      (node (ref "81-88") (pin "8") (pinfunction "8_8") (pintype "passive"))
      (node (ref "SWITCH6") (pin "31") (pinfunction "Y0_31") (pintype "passive"))
    )
    (net (code "111") (name "Net-(SWITCH6-Y1)") (class "Default")
      (node (ref "81-88") (pin "7") (pinfunction "7_7") (pintype "passive"))
      (node (ref "SWITCH6") (pin "32") (pinfunction "Y1_32") (pintype "passive"))
    )
    (net (code "112") (name "Net-(SWITCH6-Y2)") (class "Default")
      (node (ref "81-88") (pin "6") (pinfunction "6_6") (pintype "passive"))
      (node (ref "SWITCH6") (pin "33") (pinfunction "Y2_33") (pintype "passive"))
    )
    (net (code "113") (name "Net-(SWITCH6-Y3)") (class "Default")
      (node (ref "81-88") (pin "5") (pinfunction "5_5") (pintype "passive"))
      (node (ref "SWITCH6") (pin "34") (pinfunction "Y3_34") (pintype "passive"))
    )
    (net (code "114") (name "Net-(SWITCH6-Y4)") (class "Default")
      (node (ref "81-88") (pin "4") (pinfunction "4_4") (pintype "passive"))
      (node (ref "SWITCH6") (pin "35") (pinfunction "Y4_35") (pintype "passive"))
    )
    (net (code "115") (name "Net-(SWITCH6-Y5)") (class "Default")
      (node (ref "81-88") (pin "3") (pinfunction "3_3") (pintype "passive"))
      (node (ref "SWITCH6") (pin "36") (pinfunction "Y5_36") (pintype "passive"))
    )
    (net (code "116") (name "Net-(SWITCH6-Y6)") (class "Default")
      (node (ref "81-88") (pin "2") (pinfunction "2_2") (pintype "passive"))
      (node (ref "SWITCH6") (pin "37") (pinfunction "Y6_37") (pintype "passive"))
    )
    (net (code "117") (name "Net-(SWITCH6-Y7)") (class "Default")
      (node (ref "81-88") (pin "1") (pinfunction "1_1") (pintype "passive"))
      (node (ref "SWITCH6") (pin "38") (pinfunction "Y7_38") (pintype "passive"))
    )
    (net (code "118") (name "Net-(SWITCH6-Y8)") (class "Default")
      (node (ref "89-96") (pin "1") (pinfunction "1_1") (pintype "passive"))
      (node (ref "SWITCH6") (pin "14") (pinfunction "Y8_14") (pintype "passive"))
    )
    (net (code "119") (name "Net-(SWITCH6-Y9)") (class "Default")
      (node (ref "89-96") (pin "2") (pinfunction "2_2") (pintype "passive"))
      (node (ref "SWITCH6") (pin "13") (pinfunction "Y9_13") (pintype "passive"))
    )
    (net (code "120") (name "Net-(SWITCH6-Y10)") (class "Default")
      (node (ref "89-96") (pin "3") (pinfunction "3_3") (pintype "passive"))
      (node (ref "SWITCH6") (pin "12") (pinfunction "Y10_12") (pintype "passive"))
    )
    (net (code "121") (name "Net-(SWITCH6-Y11)") (class "Default")
      (node (ref "89-96") (pin "4") (pinfunction "4_4") (pintype "passive"))
      (node (ref "SWITCH6") (pin "11") (pinfunction "Y11_11") (pintype "passive"))
    )
    (net (code "122") (name "Net-(SWITCH6-Y12)") (class "Default")
      (node (ref "89-96") (pin "5") (pinfunction "5_5") (pintype "passive"))
      (node (ref "SWITCH6") (pin "10") (pinfunction "Y12_10") (pintype "passive"))
    )
    (net (code "123") (name "Net-(SWITCH6-Y13)") (class "Default")
      (node (ref "89-96") (pin "6") (pinfunction "6_6") (pintype "passive"))
      (node (ref "SWITCH6") (pin "9") (pinfunction "Y13_9") (pintype "passive"))
    )
    (net (code "124") (name "Net-(SWITCH6-Y14)") (class "Default")
      (node (ref "89-96") (pin "7") (pinfunction "7_7") (pintype "passive"))
      (node (ref "SWITCH6") (pin "8") (pinfunction "Y14_8") (pintype "passive"))
    )
    (net (code "125") (name "Net-(SWITCH6-Y15)") (class "Default")
      (node (ref "89-96") (pin "8") (pinfunction "8_8") (pintype "passive"))
      (node (ref "SWITCH6") (pin "7") (pinfunction "Y15_7") (pintype "passive"))
    )
    (net (code "126") (name "VCC") (class "Default")
      (node (ref "PICO") (pin "3V3") (pinfunction "3V3_3V3") (pintype "bidirectional"))
      (node (ref "SWITCH1") (pin "42") (pinfunction "VCC_42") (pintype "power_in"))
      (node (ref "SWITCH2") (pin "42") (pinfunction "VCC_42") (pintype "power_in"))
      (node (ref "SWITCH3") (pin "42") (pinfunction "VCC_42") (pintype "power_in"))
      (node (ref "SWITCH4") (pin "42") (pinfunction "VCC_42") (pintype "power_in"))
      (node (ref "SWITCH5") (pin "42") (pinfunction "VCC_42") (pintype "power_in"))
      (node (ref "SWITCH6") (pin "42") (pinfunction "VCC_42") (pintype "power_in"))
    )
    (net (code "127") (name "VDD") (class "Default")
      (node (ref "SWITCH1") (pin "41") (pinfunction "VDD_41") (pintype "power_in"))
      (node (ref "SWITCH2") (pin "41") (pinfunction "VDD_41") (pintype "power_in"))
      (node (ref "SWITCH3") (pin "41") (pinfunction "VDD_41") (pintype "power_in"))
      (node (ref "SWITCH4") (pin "41") (pinfunction "VDD_41") (pintype "power_in"))
      (node (ref "SWITCH5") (pin "41") (pinfunction "VDD_41") (pintype "power_in"))
      (node (ref "SWITCH6") (pin "41") (pinfunction "VDD_41") (pintype "power_in"))
      (node (ref "VDD/VSS") (pin "1") (pinfunction "1_1") (pintype "passive"))
    )
    (net (code "128") (name "VSS") (class "Default")
      (node (ref "SWITCH1") (pin "4") (pinfunction "VSS_4") (pintype "power_in"))
      (node (ref "SWITCH2") (pin "4") (pinfunction "VSS_4") (pintype "power_in"))
      (node (ref "SWITCH3") (pin "4") (pinfunction "VSS_4") (pintype "power_in"))
      (node (ref "SWITCH4") (pin "4") (pinfunction "VSS_4") (pintype "power_in"))
      (node (ref "SWITCH5") (pin "4") (pinfunction "VSS_4") (pintype "power_in"))
      (node (ref "SWITCH6") (pin "4") (pinfunction "VSS_4") (pintype "power_in"))
      (node (ref "VDD/VSS") (pin "2") (pinfunction "2_2") (pintype "passive"))
    )
    (net (code "129") (name "unconnected-(PICO-Pad3V3_EN)") (class "Default")
      (node (ref "PICO") (pin "3V3_EN") (pinfunction "3V3_EN_3V3_EN") (pintype "bidirectional"))
    )
    (net (code "130") (name "unconnected-(PICO-PadADC_VREF)") (class "Default")
      (node (ref "PICO") (pin "ADC_VREF") (pinfunction "ADC_VREF_ADC_VREF") (pintype "bidirectional"))
    )
    (net (code "131") (name "unconnected-(PICO-PadAGND)") (class "Default")
      (node (ref "PICO") (pin "AGND") (pinfunction "AGND_AGND") (pintype "bidirectional"))
    )
    (net (code "132") (name "unconnected-(PICO-PadGP6)") (class "Default")
      (node (ref "PICO") (pin "GP6") (pinfunction "GP6_GP6") (pintype "bidirectional"))
    )
    (net (code "133") (name "unconnected-(PICO-PadGP7)") (class "Default")
      (node (ref "PICO") (pin "GP7") (pinfunction "GP7_GP7") (pintype "bidirectional"))
    )
    (net (code "134") (name "unconnected-(PICO-PadGP8)") (class "Default")
      (node (ref "PICO") (pin "GP8") (pinfunction "GP8_GP8") (pintype "bidirectional"))
    )
    (net (code "135") (name "unconnected-(PICO-PadGP9)") (class "Default")
      (node (ref "PICO") (pin "GP9") (pinfunction "GP9_GP9") (pintype "bidirectional"))
    )
    (net (code "136") (name "unconnected-(PICO-PadGP10)") (class "Default")
      (node (ref "PICO") (pin "GP10") (pinfunction "GP10_GP10") (pintype "bidirectional"))
    )
    (net (code "137") (name "unconnected-(PICO-PadGP11)") (class "Default")
      (node (ref "PICO") (pin "GP11") (pinfunction "GP11_GP11") (pintype "bidirectional"))
    )
    (net (code "138") (name "unconnected-(PICO-PadGP12)") (class "Default")
      (node (ref "PICO") (pin "GP12") (pinfunction "GP12_GP12") (pintype "bidirectional"))
    )
    (net (code "139") (name "unconnected-(PICO-PadGP13)") (class "Default")
      (node (ref "PICO") (pin "GP13") (pinfunction "GP13_GP13") (pintype "bidirectional"))
    )
    (net (code "140") (name "unconnected-(PICO-PadGP14)") (class "Default")
      (node (ref "PICO") (pin "GP14") (pinfunction "GP14_GP14") (pintype "bidirectional"))
    )
    (net (code "141") (name "unconnected-(PICO-PadGP15)") (class "Default")
      (node (ref "PICO") (pin "GP15") (pinfunction "GP15_GP15") (pintype "bidirectional"))
    )
    (net (code "142") (name "unconnected-(PICO-PadGP16)") (class "Default")
      (node (ref "PICO") (pin "GP16") (pinfunction "GP16_GP16") (pintype "bidirectional"))
    )
    (net (code "143") (name "unconnected-(PICO-PadGP17)") (class "Default")
      (node (ref "PICO") (pin "GP17") (pinfunction "GP17_GP17") (pintype "bidirectional"))
    )
    (net (code "144") (name "unconnected-(PICO-PadGP18)") (class "Default")
      (node (ref "PICO") (pin "GP18") (pinfunction "GP18_GP18") (pintype "bidirectional"))
    )
    (net (code "145") (name "unconnected-(PICO-PadGP19)") (class "Default")
      (node (ref "PICO") (pin "GP19") (pinfunction "GP19_GP19") (pintype "bidirectional"))
    )
    (net (code "146") (name "unconnected-(PICO-PadGP20)") (class "Default")
      (node (ref "PICO") (pin "GP20") (pinfunction "GP20_GP20") (pintype "bidirectional"))
    )
    (net (code "147") (name "unconnected-(PICO-PadGP21)") (class "Default")
      (node (ref "PICO") (pin "GP21") (pinfunction "GP21_GP21") (pintype "bidirectional"))
    )
    (net (code "148") (name "unconnected-(PICO-PadGP22)") (class "Default")
      (node (ref "PICO") (pin "GP22") (pinfunction "GP22_GP22") (pintype "bidirectional"))
    )
    (net (code "149") (name "unconnected-(PICO-PadGP26_A0)") (class "Default")
      (node (ref "PICO") (pin "GP26_A0") (pinfunction "GP26_A0_GP26_A0") (pintype "bidirectional"))
    )
    (net (code "150") (name "unconnected-(PICO-PadGP27_A1)") (class "Default")
      (node (ref "PICO") (pin "GP27_A1") (pinfunction "GP27_A1_GP27_A1") (pintype "bidirectional"))
    )
    (net (code "151") (name "unconnected-(PICO-PadGP28_A2)") (class "Default")
      (node (ref "PICO") (pin "GP28_A2") (pinfunction "GP28_A2_GP28_A2") (pintype "bidirectional"))
    )
    (net (code "152") (name "unconnected-(PICO-PadRUN)") (class "Default")
      (node (ref "PICO") (pin "RUN") (pinfunction "RUN_RUN") (pintype "bidirectional"))
    )
    (net (code "153") (name "unconnected-(PICO-PadSWCLK)") (class "Default")
      (node (ref "PICO") (pin "SWCLK") (pinfunction "SWCLK_SWCLK") (pintype "bidirectional"))
    )
    (net (code "154") (name "unconnected-(PICO-PadSWDIO)") (class "Default")
      (node (ref "PICO") (pin "SWDIO") (pinfunction "SWDIO_SWDIO") (pintype "bidirectional"))
    )
    (net (code "155") (name "unconnected-(PICO-PadVBUS)") (class "Default")
      (node (ref "PICO") (pin "VBUS") (pinfunction "VBUS_VBUS") (pintype "bidirectional"))
    )
    (net (code "156") (name "unconnected-(PICO-PadVSYS)") (class "Default")
      (node (ref "PICO") (pin "VSYS") (pinfunction "VSYS_VSYS") (pintype "bidirectional"))
    )
    (net (code "157") (name "unconnected-(SWITCH1-NC-Pad40)") (class "Default")
      (node (ref "SWITCH1") (pin "40") (pinfunction "NC_40") (pintype "passive"))
    )
    (net (code "158") (name "unconnected-(SWITCH1-NC_2-Pad5)") (class "Default")
      (node (ref "SWITCH1") (pin "5") (pinfunction "NC_2_5") (pintype "passive"))
    )
    (net (code "159") (name "unconnected-(SWITCH1-NC_3-Pad6)") (class "Default")
      (node (ref "SWITCH1") (pin "6") (pinfunction "NC_3_6") (pintype "passive"))
    )
    (net (code "160") (name "unconnected-(SWITCH1-NC_4-Pad39)") (class "Default")
      (node (ref "SWITCH1") (pin "39") (pinfunction "NC_4_39") (pintype "passive"))
    )
    (net (code "161") (name "unconnected-(SWITCH2-NC-Pad40)") (class "Default")
      (node (ref "SWITCH2") (pin "40") (pinfunction "NC_40") (pintype "passive"))
    )
    (net (code "162") (name "unconnected-(SWITCH2-NC_2-Pad5)") (class "Default")
      (node (ref "SWITCH2") (pin "5") (pinfunction "NC_2_5") (pintype "passive"))
    )
    (net (code "163") (name "unconnected-(SWITCH2-NC_3-Pad6)") (class "Default")
      (node (ref "SWITCH2") (pin "6") (pinfunction "NC_3_6") (pintype "passive"))
    )
    (net (code "164") (name "unconnected-(SWITCH2-NC_4-Pad39)") (class "Default")
      (node (ref "SWITCH2") (pin "39") (pinfunction "NC_4_39") (pintype "passive"))
    )
    (net (code "165") (name "unconnected-(SWITCH3-NC-Pad40)") (class "Default")
      (node (ref "SWITCH3") (pin "40") (pinfunction "NC_40") (pintype "passive"))
    )
    (net (code "166") (name "unconnected-(SWITCH3-NC_2-Pad5)") (class "Default")
      (node (ref "SWITCH3") (pin "5") (pinfunction "NC_2_5") (pintype "passive"))
    )
    (net (code "167") (name "unconnected-(SWITCH3-NC_3-Pad6)") (class "Default")
      (node (ref "SWITCH3") (pin "6") (pinfunction "NC_3_6") (pintype "passive"))
    )
    (net (code "168") (name "unconnected-(SWITCH3-NC_4-Pad39)") (class "Default")
      (node (ref "SWITCH3") (pin "39") (pinfunction "NC_4_39") (pintype "passive"))
    )
    (net (code "169") (name "unconnected-(SWITCH4-NC-Pad40)") (class "Default")
      (node (ref "SWITCH4") (pin "40") (pinfunction "NC_40") (pintype "passive"))
    )
    (net (code "170") (name "unconnected-(SWITCH4-NC_2-Pad5)") (class "Default")
      (node (ref "SWITCH4") (pin "5") (pinfunction "NC_2_5") (pintype "passive"))
    )
    (net (code "171") (name "unconnected-(SWITCH4-NC_3-Pad6)") (class "Default")
      (node (ref "SWITCH4") (pin "6") (pinfunction "NC_3_6") (pintype "passive"))
    )
    (net (code "172") (name "unconnected-(SWITCH4-NC_4-Pad39)") (class "Default")
      (node (ref "SWITCH4") (pin "39") (pinfunction "NC_4_39") (pintype "passive"))
    )
    (net (code "173") (name "unconnected-(SWITCH5-NC-Pad40)") (class "Default")
      (node (ref "SWITCH5") (pin "40") (pinfunction "NC_40") (pintype "passive"))
    )
    (net (code "174") (name "unconnected-(SWITCH5-NC_2-Pad5)") (class "Default")
      (node (ref "SWITCH5") (pin "5") (pinfunction "NC_2_5") (pintype "passive"))
    )
    (net (code "175") (name "unconnected-(SWITCH5-NC_3-Pad6)") (class "Default")
      (node (ref "SWITCH5") (pin "6") (pinfunction "NC_3_6") (pintype "passive"))
    )
    (net (code "176") (name "unconnected-(SWITCH5-NC_4-Pad39)") (class "Default")
      (node (ref "SWITCH5") (pin "39") (pinfunction "NC_4_39") (pintype "passive"))
    )
    (net (code "177") (name "unconnected-(SWITCH6-NC-Pad40)") (class "Default")
      (node (ref "SWITCH6") (pin "40") (pinfunction "NC_40") (pintype "passive"))
    )
    (net (code "178") (name "unconnected-(SWITCH6-NC_2-Pad5)") (class "Default")
      (node (ref "SWITCH6") (pin "5") (pinfunction "NC_2_5") (pintype "passive"))
    )
    (net (code "179") (name "unconnected-(SWITCH6-NC_3-Pad6)") (class "Default")
      (node (ref "SWITCH6") (pin "6") (pinfunction "NC_3_6") (pintype "passive"))
    )
    (net (code "180") (name "unconnected-(SWITCH6-NC_4-Pad39)") (class "Default")
      (node (ref "SWITCH6") (pin "39") (pinfunction "NC_4_39") (pintype "passive"))
    )
    (net (code "181") (name "unconnected-(SWITCH6-SOUT-Pad44)") (class "Default")
      (node (ref "SWITCH6") (pin "44") (pinfunction "SOUT_44") (pintype "passive"))
    )
  )
)
